# OutputIndicator_20_pins_v1p0.net
KiCad netlist of a schematic drawn in EAGLE
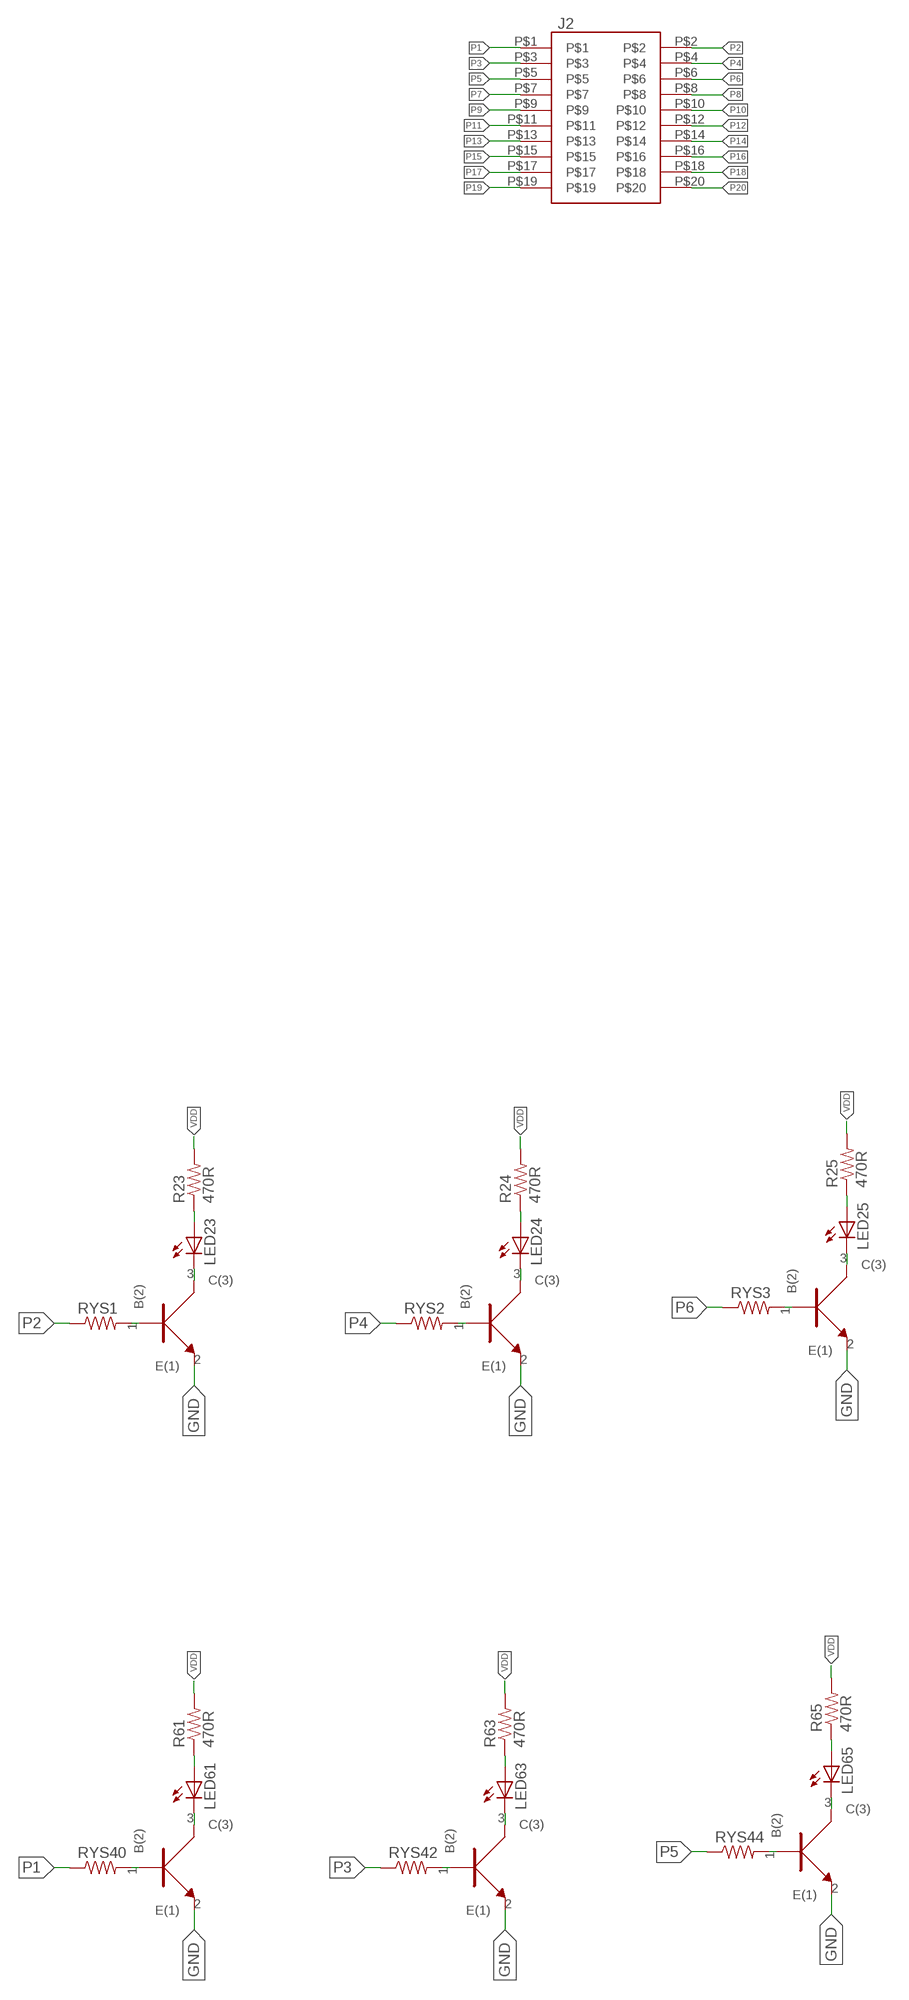
[diagram p0: schematic, sheet 1, part 1 of 2]
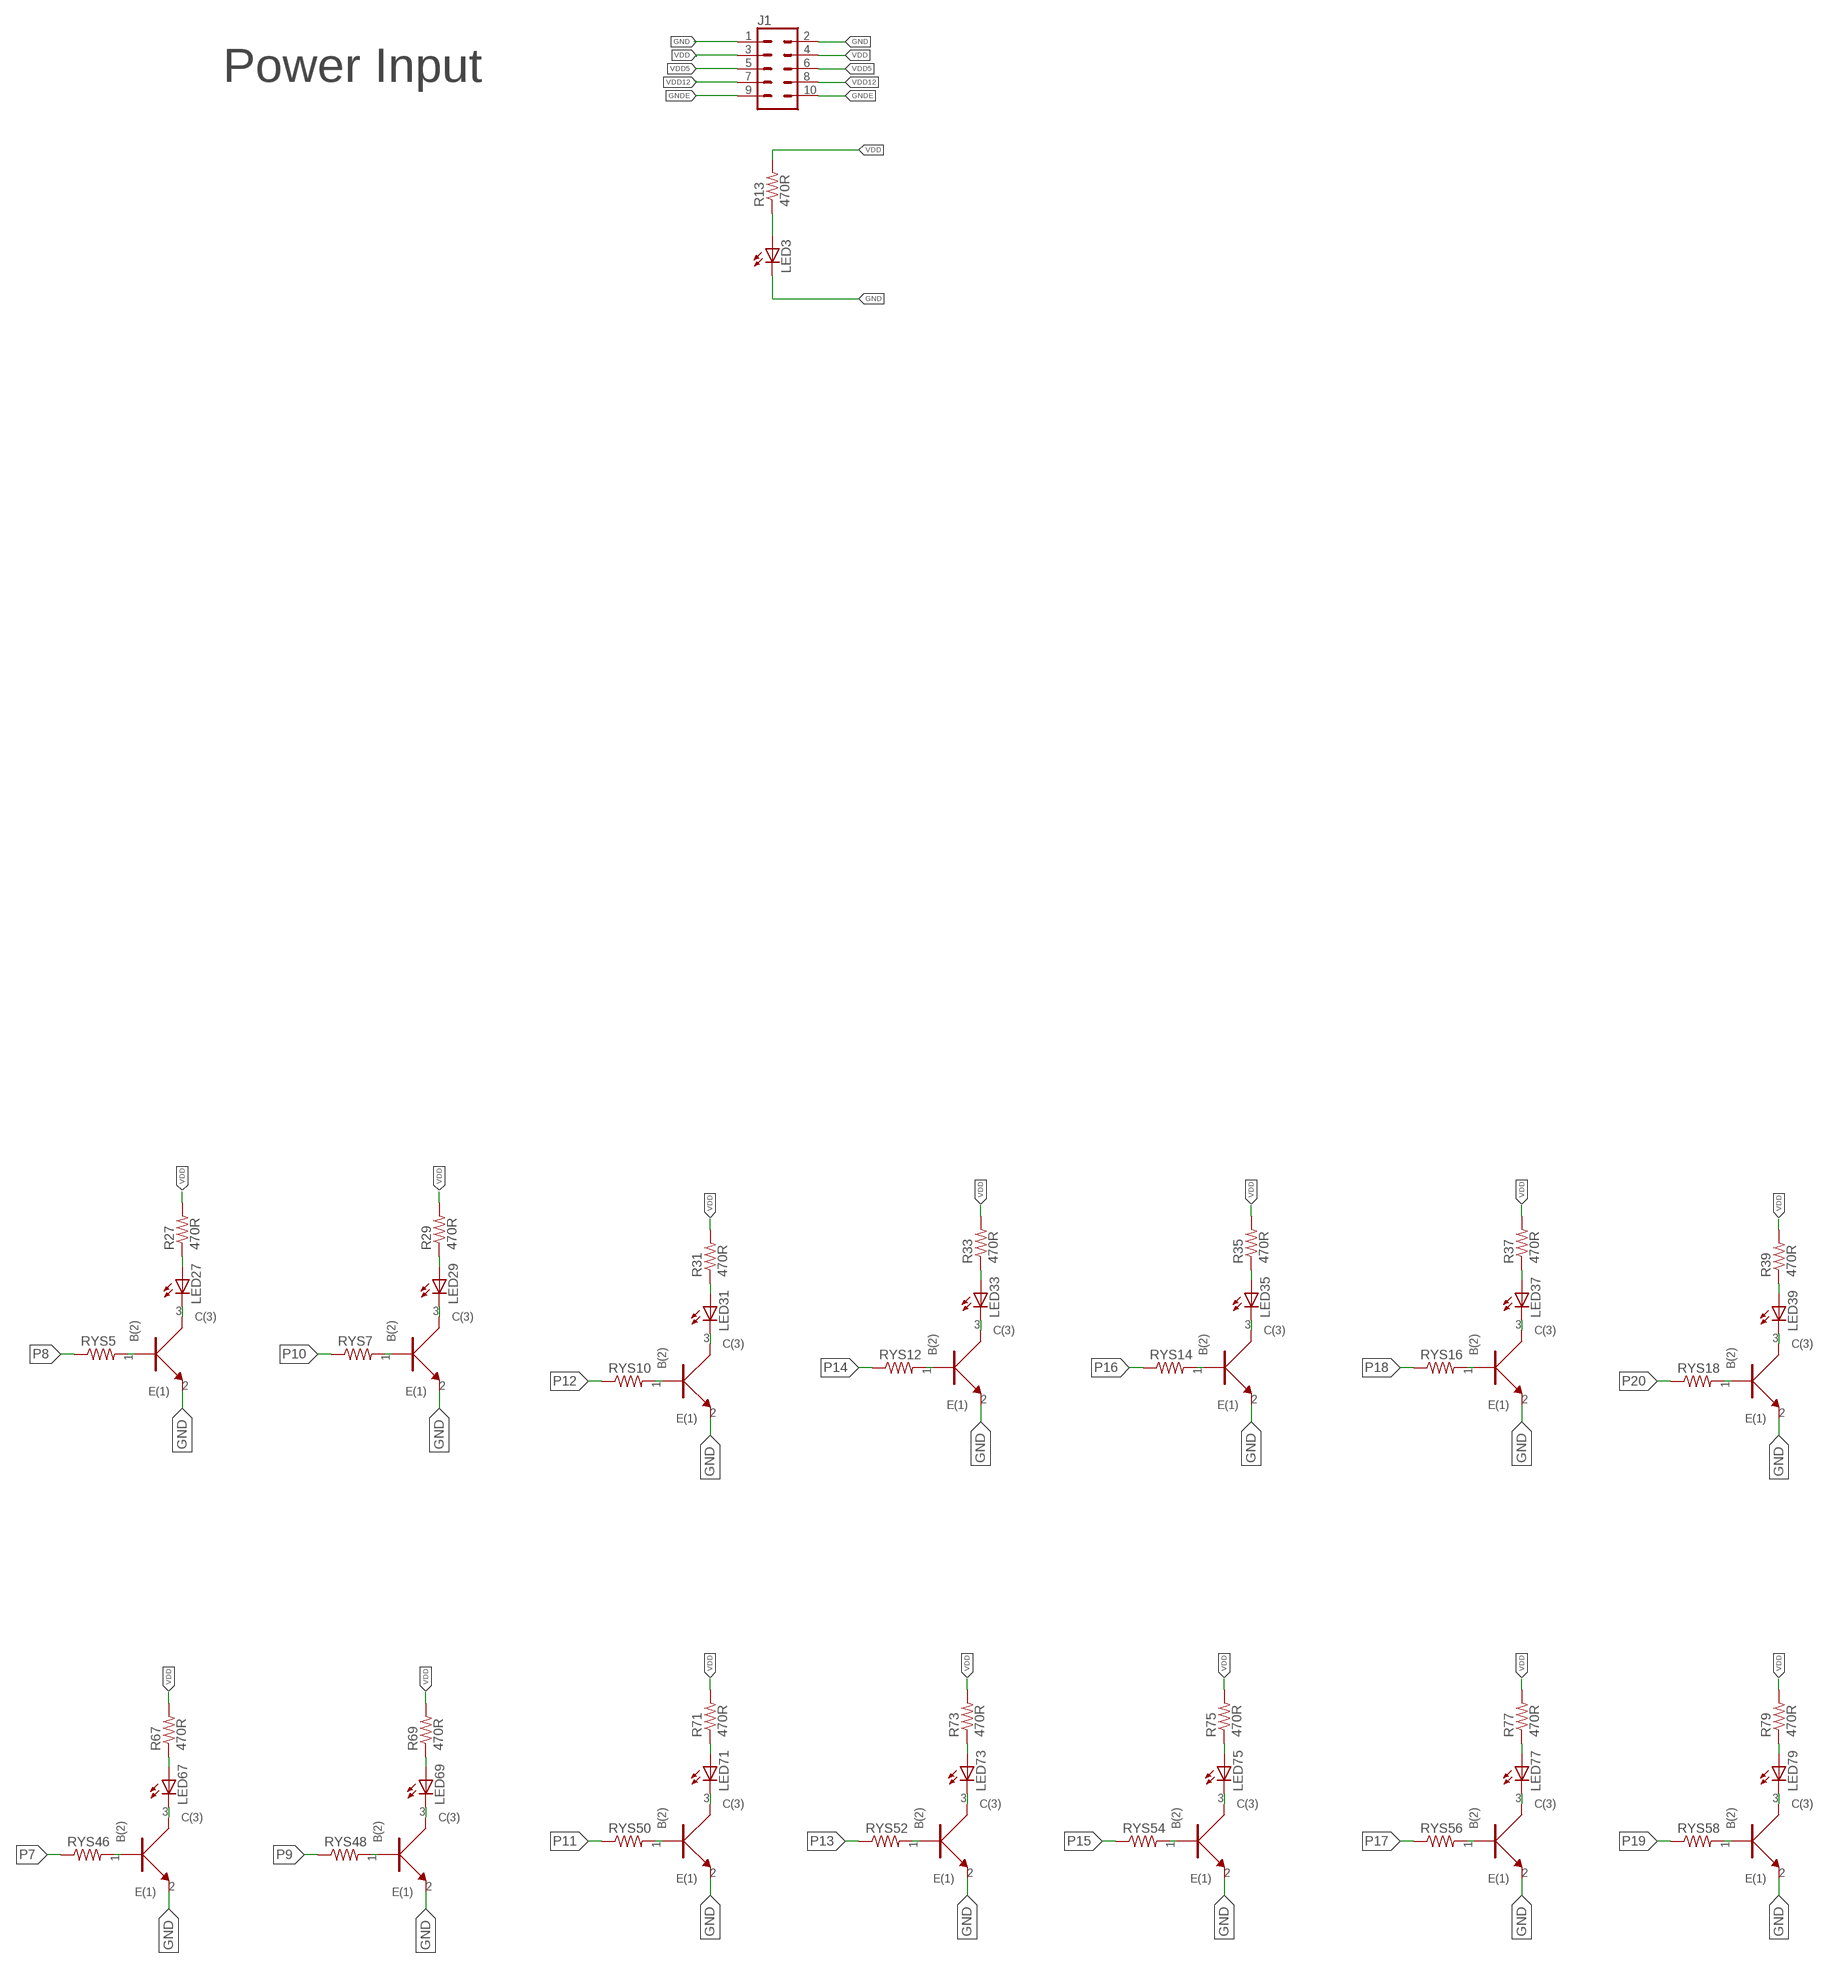
[diagram p1: schematic, sheet 1, part 2 of 2]

(export (version "E")
  (design (tool "Eeschema 10.0.6"))
  (components
    (comp (ref "J1")
      (value "CONN_05X2PTH")
      (footprint "eagle-import:2X5")
      (libsource (lib "eagle-import") (part "CONN_05X2PTH"))
    )
    (comp (ref "J2")
      (value "2_X_10_HEADER_GENERIC")
      (footprint "eagle-import:2_X_10_.1_INCH")
      (fields (field (name "PARTNO") "67996-420HLF"))
      (libsource (lib "eagle-import") (part "2_X_10_HEADER_GENERIC"))
    )
    (comp (ref "LED3")
      (value "LED_0805_GREEN")
      (footprint "eagle-import:LED_0805_GREEN")
      (libsource (lib "eagle-import") (part "LED_0805_GREEN"))
    )
    (comp (ref "LED23")
      (value "LED_0805_GREEN")
      (footprint "eagle-import:LED_0805_GREEN")
      (libsource (lib "eagle-import") (part "LED_0805_GREEN"))
    )
    (comp (ref "LED24")
      (value "LED_0805_GREEN")
      (footprint "eagle-import:LED_0805_GREEN")
      (libsource (lib "eagle-import") (part "LED_0805_GREEN"))
    )
    (comp (ref "LED25")
      (value "LED_0805_GREEN")
      (footprint "eagle-import:LED_0805_GREEN")
      (libsource (lib "eagle-import") (part "LED_0805_GREEN"))
    )
    (comp (ref "LED27")
      (value "LED_0805_GREEN")
      (footprint "eagle-import:LED_0805_GREEN")
      (libsource (lib "eagle-import") (part "LED_0805_GREEN"))
    )
    (comp (ref "LED29")
      (value "LED_0805_GREEN")
      (footprint "eagle-import:LED_0805_GREEN")
      (libsource (lib "eagle-import") (part "LED_0805_GREEN"))
    )
    (comp (ref "LED31")
      (value "LED_0805_GREEN")
      (footprint "eagle-import:LED_0805_GREEN")
      (libsource (lib "eagle-import") (part "LED_0805_GREEN"))
    )
    (comp (ref "LED33")
      (value "LED_0805_GREEN")
      (footprint "eagle-import:LED_0805_GREEN")
      (libsource (lib "eagle-import") (part "LED_0805_GREEN"))
    )
    (comp (ref "LED35")
      (value "LED_0805_GREEN")
      (footprint "eagle-import:LED_0805_GREEN")
      (libsource (lib "eagle-import") (part "LED_0805_GREEN"))
    )
    (comp (ref "LED37")
      (value "LED_0805_GREEN")
      (footprint "eagle-import:LED_0805_GREEN")
      (libsource (lib "eagle-import") (part "LED_0805_GREEN"))
    )
    (comp (ref "LED39")
      (value "LED_0805_GREEN")
      (footprint "eagle-import:LED_0805_GREEN")
      (libsource (lib "eagle-import") (part "LED_0805_GREEN"))
    )
    (comp (ref "LED61")
      (value "LED_0805_GREEN")
      (footprint "eagle-import:LED_0805_GREEN")
      (libsource (lib "eagle-import") (part "LED_0805_GREEN"))
    )
    (comp (ref "LED63")
      (value "LED_0805_GREEN")
      (footprint "eagle-import:LED_0805_GREEN")
      (libsource (lib "eagle-import") (part "LED_0805_GREEN"))
    )
    (comp (ref "LED65")
      (value "LED_0805_GREEN")
      (footprint "eagle-import:LED_0805_GREEN")
      (libsource (lib "eagle-import") (part "LED_0805_GREEN"))
    )
    (comp (ref "LED67")
      (value "LED_0805_GREEN")
      (footprint "eagle-import:LED_0805_GREEN")
      (libsource (lib "eagle-import") (part "LED_0805_GREEN"))
    )
    (comp (ref "LED69")
      (value "LED_0805_GREEN")
      (footprint "eagle-import:LED_0805_GREEN")
      (libsource (lib "eagle-import") (part "LED_0805_GREEN"))
    )
    (comp (ref "LED71")
      (value "LED_0805_GREEN")
      (footprint "eagle-import:LED_0805_GREEN")
      (libsource (lib "eagle-import") (part "LED_0805_GREEN"))
    )
    (comp (ref "LED73")
      (value "LED_0805_GREEN")
      (footprint "eagle-import:LED_0805_GREEN")
      (libsource (lib "eagle-import") (part "LED_0805_GREEN"))
    )
    (comp (ref "LED75")
      (value "LED_0805_GREEN")
      (footprint "eagle-import:LED_0805_GREEN")
      (libsource (lib "eagle-import") (part "LED_0805_GREEN"))
    )
    (comp (ref "LED77")
      (value "LED_0805_GREEN")
      (footprint "eagle-import:LED_0805_GREEN")
      (libsource (lib "eagle-import") (part "LED_0805_GREEN"))
    )
    (comp (ref "LED79")
      (value "LED_0805_GREEN")
      (footprint "eagle-import:LED_0805_GREEN")
      (libsource (lib "eagle-import") (part "LED_0805_GREEN"))
    )
    (comp (ref "R13")
      (value "470R")
      (footprint "eagle-import:0402")
      (libsource (lib "eagle-import") (part "R_0402"))
    )
    (comp (ref "R23")
      (value "470R")
      (footprint "eagle-import:0402")
      (libsource (lib "eagle-import") (part "R_0402"))
    )
    (comp (ref "R24")
      (value "470R")
      (footprint "eagle-import:0402")
      (libsource (lib "eagle-import") (part "R_0402"))
    )
    (comp (ref "R25")
      (value "470R")
      (footprint "eagle-import:0402")
      (libsource (lib "eagle-import") (part "R_0402"))
    )
    (comp (ref "R27")
      (value "470R")
      (footprint "eagle-import:0402")
      (libsource (lib "eagle-import") (part "R_0402"))
    )
    (comp (ref "R29")
      (value "470R")
      (footprint "eagle-import:0402")
      (libsource (lib "eagle-import") (part "R_0402"))
    )
    (comp (ref "R31")
      (value "470R")
      (footprint "eagle-import:0402")
      (libsource (lib "eagle-import") (part "R_0402"))
    )
    (comp (ref "R33")
      (value "470R")
      (footprint "eagle-import:0402")
      (libsource (lib "eagle-import") (part "R_0402"))
    )
    (comp (ref "R35")
      (value "470R")
      (footprint "eagle-import:0402")
      (libsource (lib "eagle-import") (part "R_0402"))
    )
    (comp (ref "R37")
      (value "470R")
      (footprint "eagle-import:0402")
      (libsource (lib "eagle-import") (part "R_0402"))
    )
    (comp (ref "R39")
      (value "470R")
      (footprint "eagle-import:0402")
      (libsource (lib "eagle-import") (part "R_0402"))
    )
    (comp (ref "R61")
      (value "470R")
      (footprint "eagle-import:0402")
      (libsource (lib "eagle-import") (part "R_0402"))
    )
    (comp (ref "R63")
      (value "470R")
      (footprint "eagle-import:0402")
      (libsource (lib "eagle-import") (part "R_0402"))
    )
    (comp (ref "R65")
      (value "470R")
      (footprint "eagle-import:0402")
      (libsource (lib "eagle-import") (part "R_0402"))
    )
    (comp (ref "R67")
      (value "470R")
      (footprint "eagle-import:0402")
      (libsource (lib "eagle-import") (part "R_0402"))
    )
    (comp (ref "R69")
      (value "470R")
      (footprint "eagle-import:0402")
      (libsource (lib "eagle-import") (part "R_0402"))
    )
    (comp (ref "R71")
      (value "470R")
      (footprint "eagle-import:0402")
      (libsource (lib "eagle-import") (part "R_0402"))
    )
    (comp (ref "R73")
      (value "470R")
      (footprint "eagle-import:0402")
      (libsource (lib "eagle-import") (part "R_0402"))
    )
    (comp (ref "R75")
      (value "470R")
      (footprint "eagle-import:0402")
      (libsource (lib "eagle-import") (part "R_0402"))
    )
    (comp (ref "R77")
      (value "470R")
      (footprint "eagle-import:0402")
      (libsource (lib "eagle-import") (part "R_0402"))
    )
    (comp (ref "R79")
      (value "470R")
      (footprint "eagle-import:0402")
      (libsource (lib "eagle-import") (part "R_0402"))
    )
    (comp (ref "RYS1")
      (value "1K")
      (footprint "eagle-import:0402")
      (libsource (lib "eagle-import") (part "R_0402"))
    )
    (comp (ref "RYS2")
      (value "1K")
      (footprint "eagle-import:0402")
      (libsource (lib "eagle-import") (part "R_0402"))
    )
    (comp (ref "RYS3")
      (value "1K")
      (footprint "eagle-import:0402")
      (libsource (lib "eagle-import") (part "R_0402"))
    )
    (comp (ref "RYS5")
      (value "1K")
      (footprint "eagle-import:0402")
      (libsource (lib "eagle-import") (part "R_0402"))
    )
    (comp (ref "RYS7")
      (value "1K")
      (footprint "eagle-import:0402")
      (libsource (lib "eagle-import") (part "R_0402"))
    )
    (comp (ref "RYS10")
      (value "1K")
      (footprint "eagle-import:0402")
      (libsource (lib "eagle-import") (part "R_0402"))
    )
    (comp (ref "RYS12")
      (value "1K")
      (footprint "eagle-import:0402")
      (libsource (lib "eagle-import") (part "R_0402"))
    )
    (comp (ref "RYS14")
      (value "1K")
      (footprint "eagle-import:0402")
      (libsource (lib "eagle-import") (part "R_0402"))
    )
    (comp (ref "RYS16")
      (value "1K")
      (footprint "eagle-import:0402")
      (libsource (lib "eagle-import") (part "R_0402"))
    )
    (comp (ref "RYS18")
      (value "1K")
      (footprint "eagle-import:0402")
      (libsource (lib "eagle-import") (part "R_0402"))
    )
    (comp (ref "RYS40")
      (value "1K")
      (footprint "eagle-import:0402")
      (libsource (lib "eagle-import") (part "R_0402"))
    )
    (comp (ref "RYS42")
      (value "1K")
      (footprint "eagle-import:0402")
      (libsource (lib "eagle-import") (part "R_0402"))
    )
    (comp (ref "RYS44")
      (value "1K")
      (footprint "eagle-import:0402")
      (libsource (lib "eagle-import") (part "R_0402"))
    )
    (comp (ref "RYS46")
      (value "1K")
      (footprint "eagle-import:0402")
      (libsource (lib "eagle-import") (part "R_0402"))
    )
    (comp (ref "RYS48")
      (value "1K")
      (footprint "eagle-import:0402")
      (libsource (lib "eagle-import") (part "R_0402"))
    )
    (comp (ref "RYS50")
      (value "1K")
      (footprint "eagle-import:0402")
      (libsource (lib "eagle-import") (part "R_0402"))
    )
    (comp (ref "RYS52")
      (value "1K")
      (footprint "eagle-import:0402")
      (libsource (lib "eagle-import") (part "R_0402"))
    )
    (comp (ref "RYS54")
      (value "1K")
      (footprint "eagle-import:0402")
      (libsource (lib "eagle-import") (part "R_0402"))
    )
    (comp (ref "RYS56")
      (value "1K")
      (footprint "eagle-import:0402")
      (libsource (lib "eagle-import") (part "R_0402"))
    )
    (comp (ref "RYS58")
      (value "1K")
      (footprint "eagle-import:0402")
      (libsource (lib "eagle-import") (part "R_0402"))
    )
    (comp (ref "U1")
      (value "BC846BW")
      (footprint "eagle-import:SOT323")
      (libsource (lib "eagle-import") (part "BC846BW"))
    )
    (comp (ref "U2")
      (value "BC846BW")
      (footprint "eagle-import:SOT323")
      (libsource (lib "eagle-import") (part "BC846BW"))
    )
    (comp (ref "U3")
      (value "BC846BW")
      (footprint "eagle-import:SOT323")
      (libsource (lib "eagle-import") (part "BC846BW"))
    )
    (comp (ref "U5")
      (value "BC846BW")
      (footprint "eagle-import:SOT323")
      (libsource (lib "eagle-import") (part "BC846BW"))
    )
    (comp (ref "U7")
      (value "BC846BW")
      (footprint "eagle-import:SOT323")
      (libsource (lib "eagle-import") (part "BC846BW"))
    )
    (comp (ref "U9")
      (value "BC846BW")
      (footprint "eagle-import:SOT323")
      (libsource (lib "eagle-import") (part "BC846BW"))
    )
    (comp (ref "U11")
      (value "BC846BW")
      (footprint "eagle-import:SOT323")
      (libsource (lib "eagle-import") (part "BC846BW"))
    )
    (comp (ref "U13")
      (value "BC846BW")
      (footprint "eagle-import:SOT323")
      (libsource (lib "eagle-import") (part "BC846BW"))
    )
    (comp (ref "U15")
      (value "BC846BW")
      (footprint "eagle-import:SOT323")
      (libsource (lib "eagle-import") (part "BC846BW"))
    )
    (comp (ref "U17")
      (value "BC846BW")
      (footprint "eagle-import:SOT323")
      (libsource (lib "eagle-import") (part "BC846BW"))
    )
    (comp (ref "U40")
      (value "BC846BW")
      (footprint "eagle-import:SOT323")
      (libsource (lib "eagle-import") (part "BC846BW"))
    )
    (comp (ref "U42")
      (value "BC846BW")
      (footprint "eagle-import:SOT323")
      (libsource (lib "eagle-import") (part "BC846BW"))
    )
    (comp (ref "U44")
      (value "BC846BW")
      (footprint "eagle-import:SOT323")
      (libsource (lib "eagle-import") (part "BC846BW"))
    )
    (comp (ref "U46")
      (value "BC846BW")
      (footprint "eagle-import:SOT323")
      (libsource (lib "eagle-import") (part "BC846BW"))
    )
    (comp (ref "U48")
      (value "BC846BW")
      (footprint "eagle-import:SOT323")
      (libsource (lib "eagle-import") (part "BC846BW"))
    )
    (comp (ref "U50")
      (value "BC846BW")
      (footprint "eagle-import:SOT323")
      (libsource (lib "eagle-import") (part "BC846BW"))
    )
    (comp (ref "U52")
      (value "BC846BW")
      (footprint "eagle-import:SOT323")
      (libsource (lib "eagle-import") (part "BC846BW"))
    )
    (comp (ref "U54")
      (value "BC846BW")
      (footprint "eagle-import:SOT323")
      (libsource (lib "eagle-import") (part "BC846BW"))
    )
    (comp (ref "U56")
      (value "BC846BW")
      (footprint "eagle-import:SOT323")
      (libsource (lib "eagle-import") (part "BC846BW"))
    )
    (comp (ref "U58")
      (value "BC846BW")
      (footprint "eagle-import:SOT323")
      (libsource (lib "eagle-import") (part "BC846BW"))
    )
  )
  (nets
    (net (code "1") (name "GND") (class "Default")
      (node (ref "J1") (pin "1") (pinfunction "1_1") (pintype "passive"))
      (node (ref "J1") (pin "2") (pinfunction "2_2") (pintype "passive"))
      (node (ref "LED3") (pin "C") (pinfunction "C_C") (pintype "passive"))
      (node (ref "U1") (pin "2") (pinfunction "E(1)_2") (pintype "output"))
      (node (ref "U11") (pin "2") (pinfunction "E(1)_2") (pintype "output"))
      (node (ref "U13") (pin "2") (pinfunction "E(1)_2") (pintype "output"))
      (node (ref "U15") (pin "2") (pinfunction "E(1)_2") (pintype "output"))
      (node (ref "U17") (pin "2") (pinfunction "E(1)_2") (pintype "output"))
      (node (ref "U2") (pin "2") (pinfunction "E(1)_2") (pintype "output"))
      (node (ref "U3") (pin "2") (pinfunction "E(1)_2") (pintype "output"))
      (node (ref "U40") (pin "2") (pinfunction "E(1)_2") (pintype "output"))
      (node (ref "U42") (pin "2") (pinfunction "E(1)_2") (pintype "output"))
      (node (ref "U44") (pin "2") (pinfunction "E(1)_2") (pintype "output"))
      (node (ref "U46") (pin "2") (pinfunction "E(1)_2") (pintype "output"))
      (node (ref "U48") (pin "2") (pinfunction "E(1)_2") (pintype "output"))
      (node (ref "U5") (pin "2") (pinfunction "E(1)_2") (pintype "output"))
      (node (ref "U50") (pin "2") (pinfunction "E(1)_2") (pintype "output"))
      (node (ref "U52") (pin "2") (pinfunction "E(1)_2") (pintype "output"))
      (node (ref "U54") (pin "2") (pinfunction "E(1)_2") (pintype "output"))
      (node (ref "U56") (pin "2") (pinfunction "E(1)_2") (pintype "output"))
      (node (ref "U58") (pin "2") (pinfunction "E(1)_2") (pintype "output"))
      (node (ref "U7") (pin "2") (pinfunction "E(1)_2") (pintype "output"))
      (node (ref "U9") (pin "2") (pinfunction "E(1)_2") (pintype "output"))
    )
    (net (code "2") (name "GNDE") (class "Default")
      (node (ref "J1") (pin "10") (pinfunction "10_10") (pintype "passive"))
      (node (ref "J1") (pin "9") (pinfunction "9_9") (pintype "passive"))
    )
    (net (code "3") (name "Net-(R13-1)") (class "Default")
      (node (ref "LED3") (pin "A") (pinfunction "A_A") (pintype "passive"))
      (node (ref "R13") (pin "P$1") (pinfunction "1_P$1") (pintype "passive"))
    )
    (net (code "4") (name "Net-(R23-1)") (class "Default")
      (node (ref "LED23") (pin "A") (pinfunction "A_A") (pintype "passive"))
      (node (ref "R23") (pin "P$1") (pinfunction "1_P$1") (pintype "passive"))
    )
    (net (code "5") (name "Net-(R24-1)") (class "Default")
      (node (ref "LED24") (pin "A") (pinfunction "A_A") (pintype "passive"))
      (node (ref "R24") (pin "P$1") (pinfunction "1_P$1") (pintype "passive"))
    )
    (net (code "6") (name "Net-(R25-1)") (class "Default")
      (node (ref "LED25") (pin "A") (pinfunction "A_A") (pintype "passive"))
      (node (ref "R25") (pin "P$1") (pinfunction "1_P$1") (pintype "passive"))
    )
    (net (code "7") (name "Net-(R27-1)") (class "Default")
      (node (ref "LED27") (pin "A") (pinfunction "A_A") (pintype "passive"))
      (node (ref "R27") (pin "P$1") (pinfunction "1_P$1") (pintype "passive"))
    )
    (net (code "8") (name "Net-(R29-1)") (class "Default")
      (node (ref "LED29") (pin "A") (pinfunction "A_A") (pintype "passive"))
      (node (ref "R29") (pin "P$1") (pinfunction "1_P$1") (pintype "passive"))
    )
    (net (code "9") (name "Net-(R31-1)") (class "Default")
      (node (ref "LED31") (pin "A") (pinfunction "A_A") (pintype "passive"))
      (node (ref "R31") (pin "P$1") (pinfunction "1_P$1") (pintype "passive"))
    )
    (net (code "10") (name "Net-(R33-1)") (class "Default")
      (node (ref "LED33") (pin "A") (pinfunction "A_A") (pintype "passive"))
      (node (ref "R33") (pin "P$1") (pinfunction "1_P$1") (pintype "passive"))
    )
    (net (code "11") (name "Net-(R35-1)") (class "Default")
      (node (ref "LED35") (pin "A") (pinfunction "A_A") (pintype "passive"))
      (node (ref "R35") (pin "P$1") (pinfunction "1_P$1") (pintype "passive"))
    )
    (net (code "12") (name "Net-(R37-1)") (class "Default")
      (node (ref "LED37") (pin "A") (pinfunction "A_A") (pintype "passive"))
      (node (ref "R37") (pin "P$1") (pinfunction "1_P$1") (pintype "passive"))
    )
    (net (code "13") (name "Net-(R39-1)") (class "Default")
      (node (ref "LED39") (pin "A") (pinfunction "A_A") (pintype "passive"))
      (node (ref "R39") (pin "P$1") (pinfunction "1_P$1") (pintype "passive"))
    )
    (net (code "14") (name "Net-(R61-1)") (class "Default")
      (node (ref "LED61") (pin "A") (pinfunction "A_A") (pintype "passive"))
      (node (ref "R61") (pin "P$1") (pinfunction "1_P$1") (pintype "passive"))
    )
    (net (code "15") (name "Net-(R63-1)") (class "Default")
      (node (ref "LED63") (pin "A") (pinfunction "A_A") (pintype "passive"))
      (node (ref "R63") (pin "P$1") (pinfunction "1_P$1") (pintype "passive"))
    )
    (net (code "16") (name "Net-(R65-1)") (class "Default")
      (node (ref "LED65") (pin "A") (pinfunction "A_A") (pintype "passive"))
      (node (ref "R65") (pin "P$1") (pinfunction "1_P$1") (pintype "passive"))
    )
    (net (code "17") (name "Net-(R67-1)") (class "Default")
      (node (ref "LED67") (pin "A") (pinfunction "A_A") (pintype "passive"))
      (node (ref "R67") (pin "P$1") (pinfunction "1_P$1") (pintype "passive"))
    )
    (net (code "18") (name "Net-(R69-1)") (class "Default")
      (node (ref "LED69") (pin "A") (pinfunction "A_A") (pintype "passive"))
      (node (ref "R69") (pin "P$1") (pinfunction "1_P$1") (pintype "passive"))
    )
    (net (code "19") (name "Net-(R71-1)") (class "Default")
      (node (ref "LED71") (pin "A") (pinfunction "A_A") (pintype "passive"))
      (node (ref "R71") (pin "P$1") (pinfunction "1_P$1") (pintype "passive"))
    )
    (net (code "20") (name "Net-(R73-1)") (class "Default")
      (node (ref "LED73") (pin "A") (pinfunction "A_A") (pintype "passive"))
      (node (ref "R73") (pin "P$1") (pinfunction "1_P$1") (pintype "passive"))
    )
    (net (code "21") (name "Net-(R75-1)") (class "Default")
      (node (ref "LED75") (pin "A") (pinfunction "A_A") (pintype "passive"))
      (node (ref "R75") (pin "P$1") (pinfunction "1_P$1") (pintype "passive"))
    )
    (net (code "22") (name "Net-(R77-1)") (class "Default")
      (node (ref "LED77") (pin "A") (pinfunction "A_A") (pintype "passive"))
      (node (ref "R77") (pin "P$1") (pinfunction "1_P$1") (pintype "passive"))
    )
    (net (code "23") (name "Net-(R79-1)") (class "Default")
      (node (ref "LED79") (pin "A") (pinfunction "A_A") (pintype "passive"))
      (node (ref "R79") (pin "P$1") (pinfunction "1_P$1") (pintype "passive"))
    )
    (net (code "24") (name "Net-(RYS1-2)") (class "Default")
      (node (ref "RYS1") (pin "P$2") (pinfunction "2_P$2") (pintype "passive"))
      (node (ref "U1") (pin "1") (pinfunction "B(2)_1") (pintype "input"))
    )
    (net (code "25") (name "Net-(RYS2-2)") (class "Default")
      (node (ref "RYS2") (pin "P$2") (pinfunction "2_P$2") (pintype "passive"))
      (node (ref "U2") (pin "1") (pinfunction "B(2)_1") (pintype "input"))
    )
    (net (code "26") (name "Net-(RYS3-2)") (class "Default")
      (node (ref "RYS3") (pin "P$2") (pinfunction "2_P$2") (pintype "passive"))
      (node (ref "U3") (pin "1") (pinfunction "B(2)_1") (pintype "input"))
    )
    (net (code "27") (name "Net-(RYS5-2)") (class "Default")
      (node (ref "RYS5") (pin "P$2") (pinfunction "2_P$2") (pintype "passive"))
      (node (ref "U5") (pin "1") (pinfunction "B(2)_1") (pintype "input"))
    )
    (net (code "28") (name "Net-(RYS7-2)") (class "Default")
      (node (ref "RYS7") (pin "P$2") (pinfunction "2_P$2") (pintype "passive"))
      (node (ref "U7") (pin "1") (pinfunction "B(2)_1") (pintype "input"))
    )
    (net (code "29") (name "Net-(RYS10-2)") (class "Default")
      (node (ref "RYS10") (pin "P$2") (pinfunction "2_P$2") (pintype "passive"))
      (node (ref "U9") (pin "1") (pinfunction "B(2)_1") (pintype "input"))
    )
    (net (code "30") (name "Net-(RYS12-2)") (class "Default")
      (node (ref "RYS12") (pin "P$2") (pinfunction "2_P$2") (pintype "passive"))
      (node (ref "U11") (pin "1") (pinfunction "B(2)_1") (pintype "input"))
    )
    (net (code "31") (name "Net-(RYS14-2)") (class "Default")
      (node (ref "RYS14") (pin "P$2") (pinfunction "2_P$2") (pintype "passive"))
      (node (ref "U13") (pin "1") (pinfunction "B(2)_1") (pintype "input"))
    )
    (net (code "32") (name "Net-(RYS16-2)") (class "Default")
      (node (ref "RYS16") (pin "P$2") (pinfunction "2_P$2") (pintype "passive"))
      (node (ref "U15") (pin "1") (pinfunction "B(2)_1") (pintype "input"))
    )
    (net (code "33") (name "Net-(RYS18-2)") (class "Default")
      (node (ref "RYS18") (pin "P$2") (pinfunction "2_P$2") (pintype "passive"))
      (node (ref "U17") (pin "1") (pinfunction "B(2)_1") (pintype "input"))
    )
    (net (code "34") (name "Net-(RYS40-2)") (class "Default")
      (node (ref "RYS40") (pin "P$2") (pinfunction "2_P$2") (pintype "passive"))
      (node (ref "U40") (pin "1") (pinfunction "B(2)_1") (pintype "input"))
    )
    (net (code "35") (name "Net-(RYS42-2)") (class "Default")
      (node (ref "RYS42") (pin "P$2") (pinfunction "2_P$2") (pintype "passive"))
      (node (ref "U42") (pin "1") (pinfunction "B(2)_1") (pintype "input"))
    )
    (net (code "36") (name "Net-(RYS44-2)") (class "Default")
      (node (ref "RYS44") (pin "P$2") (pinfunction "2_P$2") (pintype "passive"))
      (node (ref "U44") (pin "1") (pinfunction "B(2)_1") (pintype "input"))
    )
    (net (code "37") (name "Net-(RYS46-2)") (class "Default")
      (node (ref "RYS46") (pin "P$2") (pinfunction "2_P$2") (pintype "passive"))
      (node (ref "U46") (pin "1") (pinfunction "B(2)_1") (pintype "input"))
    )
    (net (code "38") (name "Net-(RYS48-2)") (class "Default")
      (node (ref "RYS48") (pin "P$2") (pinfunction "2_P$2") (pintype "passive"))
      (node (ref "U48") (pin "1") (pinfunction "B(2)_1") (pintype "input"))
    )
    (net (code "39") (name "Net-(RYS50-2)") (class "Default")
      (node (ref "RYS50") (pin "P$2") (pinfunction "2_P$2") (pintype "passive"))
      (node (ref "U50") (pin "1") (pinfunction "B(2)_1") (pintype "input"))
    )
    (net (code "40") (name "Net-(RYS52-2)") (class "Default")
      (node (ref "RYS52") (pin "P$2") (pinfunction "2_P$2") (pintype "passive"))
      (node (ref "U52") (pin "1") (pinfunction "B(2)_1") (pintype "input"))
    )
    (net (code "41") (name "Net-(RYS54-2)") (class "Default")
      (node (ref "RYS54") (pin "P$2") (pinfunction "2_P$2") (pintype "passive"))
      (node (ref "U54") (pin "1") (pinfunction "B(2)_1") (pintype "input"))
    )
    (net (code "42") (name "Net-(RYS56-2)") (class "Default")
      (node (ref "RYS56") (pin "P$2") (pinfunction "2_P$2") (pintype "passive"))
      (node (ref "U56") (pin "1") (pinfunction "B(2)_1") (pintype "input"))
    )
    (net (code "43") (name "Net-(RYS58-2)") (class "Default")
      (node (ref "RYS58") (pin "P$2") (pinfunction "2_P$2") (pintype "passive"))
      (node (ref "U58") (pin "1") (pinfunction "B(2)_1") (pintype "input"))
    )
    (net (code "44") (name "Net-(U1-C(3))") (class "Default")
      (node (ref "LED23") (pin "C") (pinfunction "C_C") (pintype "passive"))
      (node (ref "U1") (pin "3") (pinfunction "C(3)_3") (pintype "input"))
    )
    (net (code "45") (name "Net-(U2-C(3))") (class "Default")
      (node (ref "LED24") (pin "C") (pinfunction "C_C") (pintype "passive"))
      (node (ref "U2") (pin "3") (pinfunction "C(3)_3") (pintype "input"))
    )
    (net (code "46") (name "Net-(U3-C(3))") (class "Default")
      (node (ref "LED25") (pin "C") (pinfunction "C_C") (pintype "passive"))
      (node (ref "U3") (pin "3") (pinfunction "C(3)_3") (pintype "input"))
    )
    (net (code "47") (name "Net-(U5-C(3))") (class "Default")
      (node (ref "LED27") (pin "C") (pinfunction "C_C") (pintype "passive"))
      (node (ref "U5") (pin "3") (pinfunction "C(3)_3") (pintype "input"))
    )
    (net (code "48") (name "Net-(U7-C(3))") (class "Default")
      (node (ref "LED29") (pin "C") (pinfunction "C_C") (pintype "passive"))
      (node (ref "U7") (pin "3") (pinfunction "C(3)_3") (pintype "input"))
    )
    (net (code "49") (name "Net-(U9-C(3))") (class "Default")
      (node (ref "LED31") (pin "C") (pinfunction "C_C") (pintype "passive"))
      (node (ref "U9") (pin "3") (pinfunction "C(3)_3") (pintype "input"))
    )
    (net (code "50") (name "Net-(U11-C(3))") (class "Default")
      (node (ref "LED33") (pin "C") (pinfunction "C_C") (pintype "passive"))
      (node (ref "U11") (pin "3") (pinfunction "C(3)_3") (pintype "input"))
    )
    (net (code "51") (name "Net-(U13-C(3))") (class "Default")
      (node (ref "LED35") (pin "C") (pinfunction "C_C") (pintype "passive"))
      (node (ref "U13") (pin "3") (pinfunction "C(3)_3") (pintype "input"))
    )
    (net (code "52") (name "Net-(U15-C(3))") (class "Default")
      (node (ref "LED37") (pin "C") (pinfunction "C_C") (pintype "passive"))
      (node (ref "U15") (pin "3") (pinfunction "C(3)_3") (pintype "input"))
    )
    (net (code "53") (name "Net-(U17-C(3))") (class "Default")
      (node (ref "LED39") (pin "C") (pinfunction "C_C") (pintype "passive"))
      (node (ref "U17") (pin "3") (pinfunction "C(3)_3") (pintype "input"))
    )
    (net (code "54") (name "Net-(U40-C(3))") (class "Default")
      (node (ref "LED61") (pin "C") (pinfunction "C_C") (pintype "passive"))
      (node (ref "U40") (pin "3") (pinfunction "C(3)_3") (pintype "input"))
    )
    (net (code "55") (name "Net-(U42-C(3))") (class "Default")
      (node (ref "LED63") (pin "C") (pinfunction "C_C") (pintype "passive"))
      (node (ref "U42") (pin "3") (pinfunction "C(3)_3") (pintype "input"))
    )
    (net (code "56") (name "Net-(U44-C(3))") (class "Default")
      (node (ref "LED65") (pin "C") (pinfunction "C_C") (pintype "passive"))
      (node (ref "U44") (pin "3") (pinfunction "C(3)_3") (pintype "input"))
    )
    (net (code "57") (name "Net-(U46-C(3))") (class "Default")
      (node (ref "LED67") (pin "C") (pinfunction "C_C") (pintype "passive"))
      (node (ref "U46") (pin "3") (pinfunction "C(3)_3") (pintype "input"))
    )
    (net (code "58") (name "Net-(U48-C(3))") (class "Default")
      (node (ref "LED69") (pin "C") (pinfunction "C_C") (pintype "passive"))
      (node (ref "U48") (pin "3") (pinfunction "C(3)_3") (pintype "input"))
    )
    (net (code "59") (name "Net-(U50-C(3))") (class "Default")
      (node (ref "LED71") (pin "C") (pinfunction "C_C") (pintype "passive"))
      (node (ref "U50") (pin "3") (pinfunction "C(3)_3") (pintype "input"))
    )
    (net (code "60") (name "Net-(U52-C(3))") (class "Default")
      (node (ref "LED73") (pin "C") (pinfunction "C_C") (pintype "passive"))
      (node (ref "U52") (pin "3") (pinfunction "C(3)_3") (pintype "input"))
    )
    (net (code "61") (name "Net-(U54-C(3))") (class "Default")
      (node (ref "LED75") (pin "C") (pinfunction "C_C") (pintype "passive"))
      (node (ref "U54") (pin "3") (pinfunction "C(3)_3") (pintype "input"))
    )
    (net (code "62") (name "Net-(U56-C(3))") (class "Default")
      (node (ref "LED77") (pin "C") (pinfunction "C_C") (pintype "passive"))
      (node (ref "U56") (pin "3") (pinfunction "C(3)_3") (pintype "input"))
    )
    (net (code "63") (name "Net-(U58-C(3))") (class "Default")
      (node (ref "LED79") (pin "C") (pinfunction "C_C") (pintype "passive"))
      (node (ref "U58") (pin "3") (pinfunction "C(3)_3") (pintype "input"))
    )
    (net (code "64") (name "P1") (class "Default")
      (node (ref "J2") (pin "P$1") (pinfunction "P$1_P$1") (pintype "bidirectional"))
      (node (ref "RYS40") (pin "P$1") (pinfunction "1_P$1") (pintype "passive"))
    )
    (net (code "65") (name "P2") (class "Default")
      (node (ref "J2") (pin "P$2") (pinfunction "P$2_P$2") (pintype "bidirectional"))
      (node (ref "RYS1") (pin "P$1") (pinfunction "1_P$1") (pintype "passive"))
    )
    (net (code "66") (name "P3") (class "Default")
      (node (ref "J2") (pin "P$3") (pinfunction "P$3_P$3") (pintype "bidirectional"))
      (node (ref "RYS42") (pin "P$1") (pinfunction "1_P$1") (pintype "passive"))
    )
    (net (code "67") (name "P4") (class "Default")
      (node (ref "J2") (pin "P$4") (pinfunction "P$4_P$4") (pintype "bidirectional"))
      (node (ref "RYS2") (pin "P$1") (pinfunction "1_P$1") (pintype "passive"))
    )
    (net (code "68") (name "P5") (class "Default")
      (node (ref "J2") (pin "P$5") (pinfunction "P$5_P$5") (pintype "bidirectional"))
      (node (ref "RYS44") (pin "P$1") (pinfunction "1_P$1") (pintype "passive"))
    )
    (net (code "69") (name "P6") (class "Default")
      (node (ref "J2") (pin "P$6") (pinfunction "P$6_P$6") (pintype "bidirectional"))
      (node (ref "RYS3") (pin "P$1") (pinfunction "1_P$1") (pintype "passive"))
    )
    (net (code "70") (name "P7") (class "Default")
      (node (ref "J2") (pin "P$7") (pinfunction "P$7_P$7") (pintype "bidirectional"))
      (node (ref "RYS46") (pin "P$1") (pinfunction "1_P$1") (pintype "passive"))
    )
    (net (code "71") (name "P8") (class "Default")
      (node (ref "J2") (pin "P$8") (pinfunction "P$8_P$8") (pintype "bidirectional"))
      (node (ref "RYS5") (pin "P$1") (pinfunction "1_P$1") (pintype "passive"))
    )
    (net (code "72") (name "P9") (class "Default")
      (node (ref "J2") (pin "P$9") (pinfunction "P$9_P$9") (pintype "bidirectional"))
      (node (ref "RYS48") (pin "P$1") (pinfunction "1_P$1") (pintype "passive"))
    )
    (net (code "73") (name "P10") (class "Default")
      (node (ref "J2") (pin "P$10") (pinfunction "P$10_P$10") (pintype "bidirectional"))
      (node (ref "RYS7") (pin "P$1") (pinfunction "1_P$1") (pintype "passive"))
    )
    (net (code "74") (name "P11") (class "Default")
      (node (ref "J2") (pin "P$11") (pinfunction "P$11_P$11") (pintype "bidirectional"))
      (node (ref "RYS50") (pin "P$1") (pinfunction "1_P$1") (pintype "passive"))
    )
    (net (code "75") (name "P12") (class "Default")
      (node (ref "J2") (pin "P$12") (pinfunction "P$12_P$12") (pintype "bidirectional"))
      (node (ref "RYS10") (pin "P$1") (pinfunction "1_P$1") (pintype "passive"))
    )
    (net (code "76") (name "P13") (class "Default")
      (node (ref "J2") (pin "P$13") (pinfunction "P$13_P$13") (pintype "bidirectional"))
      (node (ref "RYS52") (pin "P$1") (pinfunction "1_P$1") (pintype "passive"))
    )
    (net (code "77") (name "P14") (class "Default")
      (node (ref "J2") (pin "P$14") (pinfunction "P$14_P$14") (pintype "bidirectional"))
      (node (ref "RYS12") (pin "P$1") (pinfunction "1_P$1") (pintype "passive"))
    )
    (net (code "78") (name "P15") (class "Default")
      (node (ref "J2") (pin "P$15") (pinfunction "P$15_P$15") (pintype "bidirectional"))
      (node (ref "RYS54") (pin "P$1") (pinfunction "1_P$1") (pintype "passive"))
    )
    (net (code "79") (name "P16") (class "Default")
      (node (ref "J2") (pin "P$16") (pinfunction "P$16_P$16") (pintype "bidirectional"))
      (node (ref "RYS14") (pin "P$1") (pinfunction "1_P$1") (pintype "passive"))
    )
    (net (code "80") (name "P17") (class "Default")
      (node (ref "J2") (pin "P$17") (pinfunction "P$17_P$17") (pintype "bidirectional"))
      (node (ref "RYS56") (pin "P$1") (pinfunction "1_P$1") (pintype "passive"))
    )
    (net (code "81") (name "P18") (class "Default")
      (node (ref "J2") (pin "P$18") (pinfunction "P$18_P$18") (pintype "bidirectional"))
      (node (ref "RYS16") (pin "P$1") (pinfunction "1_P$1") (pintype "passive"))
    )
    (net (code "82") (name "P19") (class "Default")
      (node (ref "J2") (pin "P$19") (pinfunction "P$19_P$19") (pintype "bidirectional"))
      (node (ref "RYS58") (pin "P$1") (pinfunction "1_P$1") (pintype "passive"))
    )
    (net (code "83") (name "P20") (class "Default")
      (node (ref "J2") (pin "P$20") (pinfunction "P$20_P$20") (pintype "bidirectional"))
      (node (ref "RYS18") (pin "P$1") (pinfunction "1_P$1") (pintype "passive"))
    )
    (net (code "84") (name "VDD") (class "Default")
      (node (ref "J1") (pin "3") (pinfunction "3_3") (pintype "passive"))
      (node (ref "J1") (pin "4") (pinfunction "4_4") (pintype "passive"))
      (node (ref "R13") (pin "P$2") (pinfunction "2_P$2") (pintype "passive"))
      (node (ref "R23") (pin "P$2") (pinfunction "2_P$2") (pintype "passive"))
      (node (ref "R24") (pin "P$2") (pinfunction "2_P$2") (pintype "passive"))
      (node (ref "R25") (pin "P$2") (pinfunction "2_P$2") (pintype "passive"))
      (node (ref "R27") (pin "P$2") (pinfunction "2_P$2") (pintype "passive"))
      (node (ref "R29") (pin "P$2") (pinfunction "2_P$2") (pintype "passive"))
      (node (ref "R31") (pin "P$2") (pinfunction "2_P$2") (pintype "passive"))
      (node (ref "R33") (pin "P$2") (pinfunction "2_P$2") (pintype "passive"))
      (node (ref "R35") (pin "P$2") (pinfunction "2_P$2") (pintype "passive"))
      (node (ref "R37") (pin "P$2") (pinfunction "2_P$2") (pintype "passive"))
      (node (ref "R39") (pin "P$2") (pinfunction "2_P$2") (pintype "passive"))
      (node (ref "R61") (pin "P$2") (pinfunction "2_P$2") (pintype "passive"))
      (node (ref "R63") (pin "P$2") (pinfunction "2_P$2") (pintype "passive"))
      (node (ref "R65") (pin "P$2") (pinfunction "2_P$2") (pintype "passive"))
      (node (ref "R67") (pin "P$2") (pinfunction "2_P$2") (pintype "passive"))
      (node (ref "R69") (pin "P$2") (pinfunction "2_P$2") (pintype "passive"))
      (node (ref "R71") (pin "P$2") (pinfunction "2_P$2") (pintype "passive"))
      (node (ref "R73") (pin "P$2") (pinfunction "2_P$2") (pintype "passive"))
      (node (ref "R75") (pin "P$2") (pinfunction "2_P$2") (pintype "passive"))
      (node (ref "R77") (pin "P$2") (pinfunction "2_P$2") (pintype "passive"))
      (node (ref "R79") (pin "P$2") (pinfunction "2_P$2") (pintype "passive"))
    )
    (net (code "85") (name "VDD5") (class "Default")
      (node (ref "J1") (pin "5") (pinfunction "5_5") (pintype "passive"))
      (node (ref "J1") (pin "6") (pinfunction "6_6") (pintype "passive"))
    )
    (net (code "86") (name "VDD12") (class "Default")
      (node (ref "J1") (pin "7") (pinfunction "7_7") (pintype "passive"))
      (node (ref "J1") (pin "8") (pinfunction "8_8") (pintype "passive"))
    )
  )
)
